# RUMP.net
KiCad netlist of a schematic drawn in EAGLE
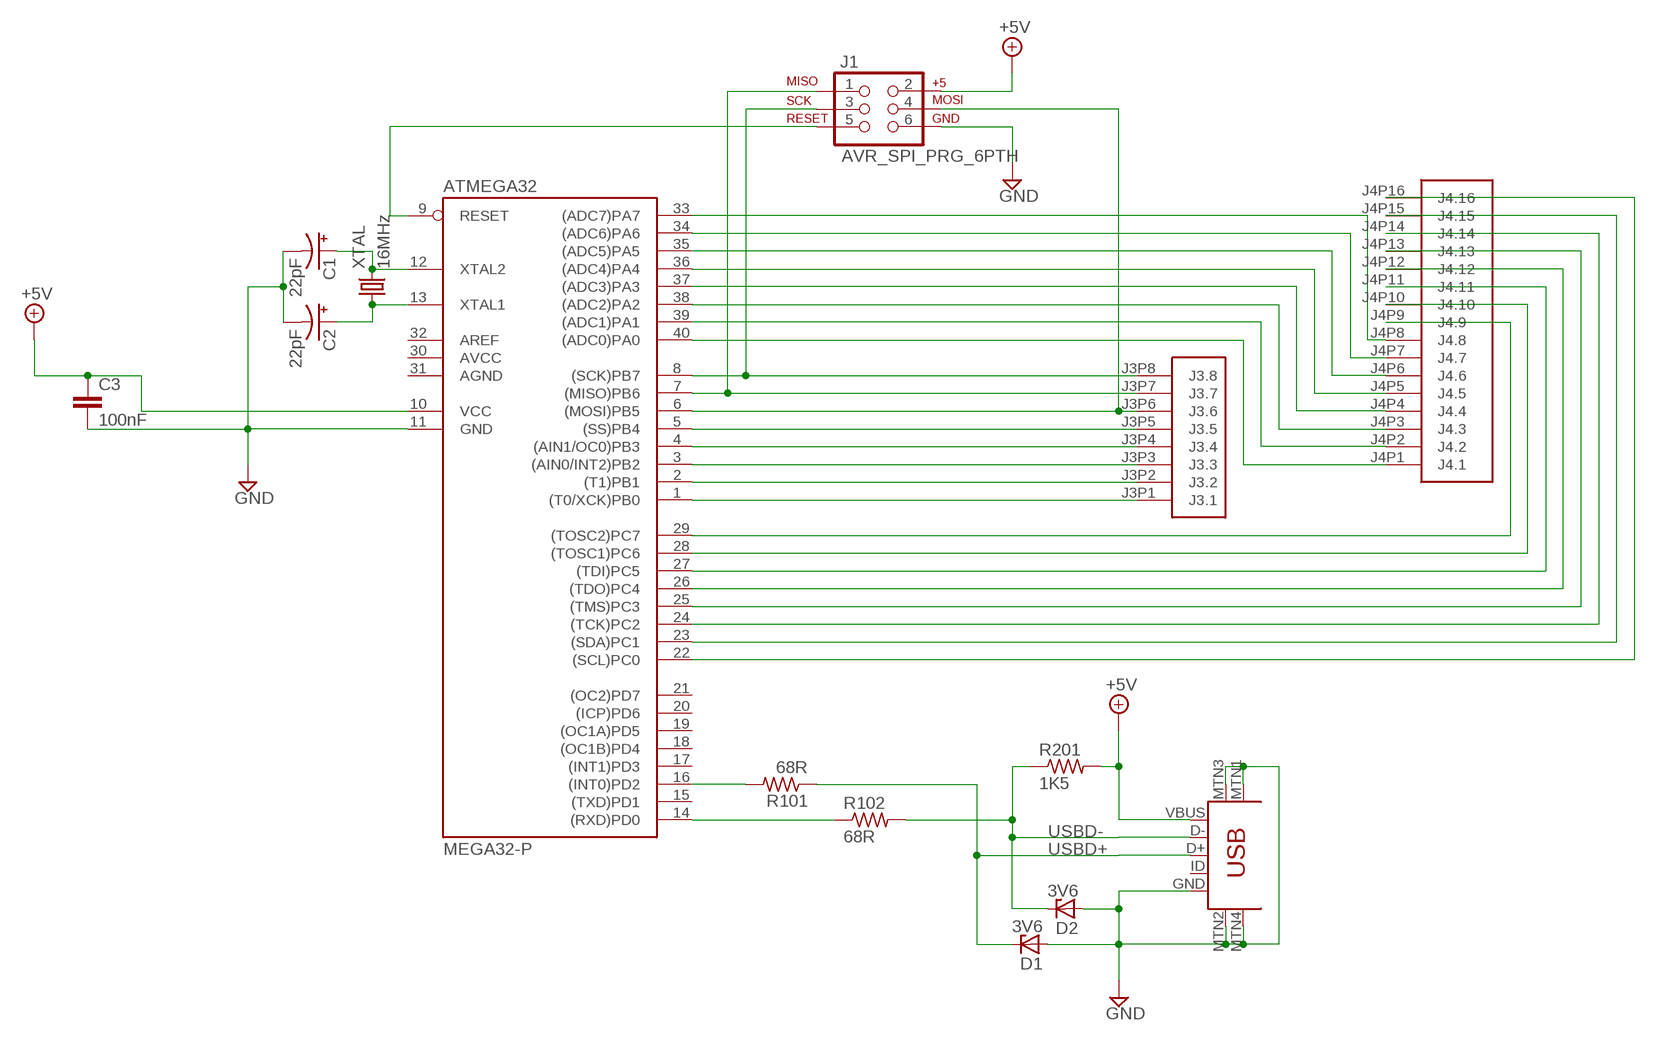
[diagram p0: schematic, sheet 1]

(export (version "E")
  (design (tool "Eeschema 10.0.6"))
  (components
    (comp (ref "ATMEGA32")
      (value "MEGA32-P")
      (footprint "eagle-import:DIL40")
      (libsource (lib "eagle-import") (part "MEGA32-P"))
    )
    (comp (ref "C1")
      (value "22pF")
      (footprint "eagle-import:E2-4")
      (libsource (lib "eagle-import") (part "CPOL-USE2-4"))
    )
    (comp (ref "C2")
      (value "22pF")
      (footprint "eagle-import:E2-4")
      (libsource (lib "eagle-import") (part "CPOL-USE2-4"))
    )
    (comp (ref "C3")
      (value "100nF")
      (footprint "eagle-import:C2.5-2")
      (libsource (lib "eagle-import") (part "C2.5/2"))
    )
    (comp (ref "D1")
      (value "3V6")
      (footprint "eagle-import:DO35Z10")
      (libsource (lib "eagle-import") (part "ZENER-DIODEDO35Z10"))
    )
    (comp (ref "D2")
      (value "3V6")
      (footprint "eagle-import:DO35Z10")
      (libsource (lib "eagle-import") (part "ZENER-DIODEDO35Z10"))
    )
    (comp (ref "J1")
      (value "AVR_SPI_PRG_6PTH")
      (footprint "eagle-import:2X3")
      (libsource (lib "eagle-import") (part "AVR_SPI_PRG_6PTH"))
    )
    (comp (ref "R101")
      (value "68R")
      (footprint "eagle-import:0204_7")
      (libsource (lib "eagle-import") (part "R-US_0204/7"))
    )
    (comp (ref "R102")
      (value "68R")
      (footprint "eagle-import:0204_7")
      (libsource (lib "eagle-import") (part "R-US_0204/7"))
    )
    (comp (ref "R201")
      (value "1K5")
      (footprint "eagle-import:0204_7")
      (libsource (lib "eagle-import") (part "R-US_0204/7"))
    )
    (comp (ref "U$1")
      (value "MODEL-M-J3")
      (footprint "eagle-import:MODEL-M-J3")
      (libsource (lib "eagle-import") (part "MODEL-M-J3"))
    )
    (comp (ref "U$2")
      (value "MODEL-M-J4")
      (footprint "eagle-import:MODEL-M-J4")
      (libsource (lib "eagle-import") (part "MODEL-M-J4"))
    )
    (comp (ref "U$3")
      (value "USB-MINIB-5PIN")
      (footprint "eagle-import:USB-MINIB")
      (libsource (lib "eagle-import") (part "USB-MINIB-5PIN"))
    )
    (comp (ref "XTAL")
      (value "16MHz")
      (footprint "eagle-import:HC49_S")
      (libsource (lib "eagle-import") (part "CRYSTALHC49S"))
    )
  )
  (nets
    (net (code "1") (name "+5V") (class "Default")
      (node (ref "ATMEGA32") (pin "10") (pinfunction "VCC_10") (pintype "power_in"))
      (node (ref "C3") (pin "1") (pinfunction "1_1") (pintype "passive"))
      (node (ref "J1") (pin "2") (pinfunction "2_2") (pintype "passive"))
      (node (ref "R201") (pin "2") (pinfunction "2_2") (pintype "passive"))
      (node (ref "U$3") (pin "VBUS") (pinfunction "VBUS_VBUS") (pintype "bidirectional"))
    )
    (net (code "2") (name "/AGND") (class "Default")
      (node (ref "ATMEGA32") (pin "31") (pinfunction "AGND_31") (pintype "power_in"))
    )
    (net (code "3") (name "/AVCC") (class "Default")
      (node (ref "ATMEGA32") (pin "30") (pinfunction "AVCC_30") (pintype "power_in"))
    )
    (net (code "4") (name "/USBD+") (class "Default")
      (node (ref "D1") (pin "C") (pinfunction "C_C") (pintype "passive"))
      (node (ref "R101") (pin "1") (pinfunction "1_1") (pintype "passive"))
      (node (ref "U$3") (pin "D+") (pinfunction "D+_D+") (pintype "bidirectional"))
    )
    (net (code "5") (name "/USBD-") (class "Default")
      (node (ref "D2") (pin "C") (pinfunction "C_C") (pintype "passive"))
      (node (ref "R102") (pin "2") (pinfunction "2_2") (pintype "passive"))
      (node (ref "R201") (pin "1") (pinfunction "1_1") (pintype "passive"))
      (node (ref "U$3") (pin "D-") (pinfunction "D-_D-") (pintype "bidirectional"))
    )
    (net (code "6") (name "GND") (class "Default")
      (node (ref "ATMEGA32") (pin "11") (pinfunction "GND_11") (pintype "power_in"))
      (node (ref "C1") (pin "-") (pinfunction "-_-") (pintype "passive"))
      (node (ref "C2") (pin "-") (pinfunction "-_-") (pintype "passive"))
      (node (ref "C3") (pin "2") (pinfunction "2_2") (pintype "passive"))
      (node (ref "D1") (pin "A") (pinfunction "A_A") (pintype "passive"))
      (node (ref "D2") (pin "A") (pinfunction "A_A") (pintype "passive"))
      (node (ref "J1") (pin "6") (pinfunction "6_6") (pintype "passive"))
      (node (ref "U$3") (pin "GND") (pinfunction "GND_GND") (pintype "bidirectional"))
      (node (ref "U$3") (pin "MTN1") (pinfunction "MTN2_MTN1") (pintype "bidirectional"))
      (node (ref "U$3") (pin "MTN2") (pinfunction "MTN3_MTN2") (pintype "bidirectional"))
      (node (ref "U$3") (pin "MTN3") (pinfunction "MTN1_MTN3") (pintype "bidirectional"))
      (node (ref "U$3") (pin "MTN4") (pinfunction "MTN4_MTN4") (pintype "bidirectional"))
    )
    (net (code "7") (name "Net-(ATMEGA32-(ADC0)PA0)") (class "Default")
      (node (ref "ATMEGA32") (pin "40") (pinfunction "(ADC0)PA0_40") (pintype "bidirectional"))
      (node (ref "U$2") (pin "J4P1") (pinfunction "J4.1_J4P1") (pintype "bidirectional"))
    )
    (net (code "8") (name "Net-(ATMEGA32-(ADC1)PA1)") (class "Default")
      (node (ref "ATMEGA32") (pin "39") (pinfunction "(ADC1)PA1_39") (pintype "bidirectional"))
      (node (ref "U$2") (pin "J4P2") (pinfunction "J4.2_J4P2") (pintype "bidirectional"))
    )
    (net (code "9") (name "Net-(ATMEGA32-(ADC2)PA2)") (class "Default")
      (node (ref "ATMEGA32") (pin "38") (pinfunction "(ADC2)PA2_38") (pintype "bidirectional"))
      (node (ref "U$2") (pin "J4P3") (pinfunction "J4.3_J4P3") (pintype "bidirectional"))
    )
    (net (code "10") (name "Net-(ATMEGA32-(ADC3)PA3)") (class "Default")
      (node (ref "ATMEGA32") (pin "37") (pinfunction "(ADC3)PA3_37") (pintype "bidirectional"))
      (node (ref "U$2") (pin "J4P4") (pinfunction "J4.4_J4P4") (pintype "bidirectional"))
    )
    (net (code "11") (name "Net-(ATMEGA32-(ADC4)PA4)") (class "Default")
      (node (ref "ATMEGA32") (pin "36") (pinfunction "(ADC4)PA4_36") (pintype "bidirectional"))
      (node (ref "U$2") (pin "J4P5") (pinfunction "J4.5_J4P5") (pintype "bidirectional"))
    )
    (net (code "12") (name "Net-(ATMEGA32-(ADC5)PA5)") (class "Default")
      (node (ref "ATMEGA32") (pin "35") (pinfunction "(ADC5)PA5_35") (pintype "bidirectional"))
      (node (ref "U$2") (pin "J4P6") (pinfunction "J4.6_J4P6") (pintype "bidirectional"))
    )
    (net (code "13") (name "Net-(ATMEGA32-(ADC6)PA6)") (class "Default")
      (node (ref "ATMEGA32") (pin "34") (pinfunction "(ADC6)PA6_34") (pintype "bidirectional"))
      (node (ref "U$2") (pin "J4P7") (pinfunction "J4.7_J4P7") (pintype "bidirectional"))
    )
    (net (code "14") (name "Net-(ATMEGA32-(ADC7)PA7)") (class "Default")
      (node (ref "ATMEGA32") (pin "33") (pinfunction "(ADC7)PA7_33") (pintype "bidirectional"))
      (node (ref "U$2") (pin "J4P8") (pinfunction "J4.8_J4P8") (pintype "bidirectional"))
    )
    (net (code "15") (name "Net-(ATMEGA32-(AIN0{slash}INT2)PB2)") (class "Default")
      (node (ref "ATMEGA32") (pin "3") (pinfunction "(AIN0/INT2)PB2_3") (pintype "bidirectional"))
      (node (ref "U$1") (pin "J3P3") (pinfunction "J3.3_J3P3") (pintype "bidirectional"))
    )
    (net (code "16") (name "Net-(ATMEGA32-(AIN1{slash}OC0)PB3)") (class "Default")
      (node (ref "ATMEGA32") (pin "4") (pinfunction "(AIN1/OC0)PB3_4") (pintype "bidirectional"))
      (node (ref "U$1") (pin "J3P4") (pinfunction "J3.4_J3P4") (pintype "bidirectional"))
    )
    (net (code "17") (name "Net-(ATMEGA32-(INT0)PD2)") (class "Default")
      (node (ref "ATMEGA32") (pin "16") (pinfunction "(INT0)PD2_16") (pintype "bidirectional"))
      (node (ref "R101") (pin "2") (pinfunction "2_2") (pintype "passive"))
    )
    (net (code "18") (name "Net-(ATMEGA32-(MISO)PB6)") (class "Default")
      (node (ref "ATMEGA32") (pin "7") (pinfunction "(MISO)PB6_7") (pintype "bidirectional"))
      (node (ref "J1") (pin "1") (pinfunction "1_1") (pintype "passive"))
      (node (ref "U$1") (pin "J3P7") (pinfunction "J3.7_J3P7") (pintype "bidirectional"))
    )
    (net (code "19") (name "Net-(ATMEGA32-(MOSI)PB5)") (class "Default")
      (node (ref "ATMEGA32") (pin "6") (pinfunction "(MOSI)PB5_6") (pintype "bidirectional"))
      (node (ref "J1") (pin "4") (pinfunction "4_4") (pintype "passive"))
      (node (ref "U$1") (pin "J3P6") (pinfunction "J3.6_J3P6") (pintype "bidirectional"))
    )
    (net (code "20") (name "Net-(ATMEGA32-(RXD)PD0)") (class "Default")
      (node (ref "ATMEGA32") (pin "14") (pinfunction "(RXD)PD0_14") (pintype "bidirectional"))
      (node (ref "R102") (pin "1") (pinfunction "1_1") (pintype "passive"))
    )
    (net (code "21") (name "Net-(ATMEGA32-(SCK)PB7)") (class "Default")
      (node (ref "ATMEGA32") (pin "8") (pinfunction "(SCK)PB7_8") (pintype "bidirectional"))
      (node (ref "J1") (pin "3") (pinfunction "3_3") (pintype "passive"))
      (node (ref "U$1") (pin "J3P8") (pinfunction "J3.8_J3P8") (pintype "bidirectional"))
    )
    (net (code "22") (name "Net-(ATMEGA32-(SCL)PC0)") (class "Default")
      (node (ref "ATMEGA32") (pin "22") (pinfunction "(SCL)PC0_22") (pintype "bidirectional"))
      (node (ref "U$2") (pin "J4P16") (pinfunction "J4.16_J4P16") (pintype "bidirectional"))
    )
    (net (code "23") (name "Net-(ATMEGA32-(SDA)PC1)") (class "Default")
      (node (ref "ATMEGA32") (pin "23") (pinfunction "(SDA)PC1_23") (pintype "bidirectional"))
      (node (ref "U$2") (pin "J4P15") (pinfunction "J4.15_J4P15") (pintype "bidirectional"))
    )
    (net (code "24") (name "Net-(ATMEGA32-(SS)PB4)") (class "Default")
      (node (ref "ATMEGA32") (pin "5") (pinfunction "(SS)PB4_5") (pintype "bidirectional"))
      (node (ref "U$1") (pin "J3P5") (pinfunction "J3.5_J3P5") (pintype "bidirectional"))
    )
    (net (code "25") (name "Net-(ATMEGA32-(T0{slash}XCK)PB0)") (class "Default")
      (node (ref "ATMEGA32") (pin "1") (pinfunction "(T0/XCK)PB0_1") (pintype "bidirectional"))
      (node (ref "U$1") (pin "J3P1") (pinfunction "J3.1_J3P1") (pintype "bidirectional"))
    )
    (net (code "26") (name "Net-(ATMEGA32-(T1)PB1)") (class "Default")
      (node (ref "ATMEGA32") (pin "2") (pinfunction "(T1)PB1_2") (pintype "bidirectional"))
      (node (ref "U$1") (pin "J3P2") (pinfunction "J3.2_J3P2") (pintype "bidirectional"))
    )
    (net (code "27") (name "Net-(ATMEGA32-(TCK)PC2)") (class "Default")
      (node (ref "ATMEGA32") (pin "24") (pinfunction "(TCK)PC2_24") (pintype "bidirectional"))
      (node (ref "U$2") (pin "J4P14") (pinfunction "J4.14_J4P14") (pintype "bidirectional"))
    )
    (net (code "28") (name "Net-(ATMEGA32-(TDI)PC5)") (class "Default")
      (node (ref "ATMEGA32") (pin "27") (pinfunction "(TDI)PC5_27") (pintype "bidirectional"))
      (node (ref "U$2") (pin "J4P11") (pinfunction "J4.11_J4P11") (pintype "bidirectional"))
    )
    (net (code "29") (name "Net-(ATMEGA32-(TDO)PC4)") (class "Default")
      (node (ref "ATMEGA32") (pin "26") (pinfunction "(TDO)PC4_26") (pintype "bidirectional"))
      (node (ref "U$2") (pin "J4P12") (pinfunction "J4.12_J4P12") (pintype "bidirectional"))
    )
    (net (code "30") (name "Net-(ATMEGA32-(TMS)PC3)") (class "Default")
      (node (ref "ATMEGA32") (pin "25") (pinfunction "(TMS)PC3_25") (pintype "bidirectional"))
      (node (ref "U$2") (pin "J4P13") (pinfunction "J4.13_J4P13") (pintype "bidirectional"))
    )
    (net (code "31") (name "Net-(ATMEGA32-(TOSC1)PC6)") (class "Default")
      (node (ref "ATMEGA32") (pin "28") (pinfunction "(TOSC1)PC6_28") (pintype "bidirectional"))
      (node (ref "U$2") (pin "J4P10") (pinfunction "J4.10_J4P10") (pintype "bidirectional"))
    )
    (net (code "32") (name "Net-(ATMEGA32-(TOSC2)PC7)") (class "Default")
      (node (ref "ATMEGA32") (pin "29") (pinfunction "(TOSC2)PC7_29") (pintype "bidirectional"))
      (node (ref "U$2") (pin "J4P9") (pinfunction "J4.9_J4P9") (pintype "bidirectional"))
    )
    (net (code "33") (name "Net-(ATMEGA32-RESET)") (class "Default")
      (node (ref "ATMEGA32") (pin "9") (pinfunction "RESET_9") (pintype "input"))
      (node (ref "J1") (pin "5") (pinfunction "5_5") (pintype "passive"))
    )
    (net (code "34") (name "Net-(ATMEGA32-XTAL1)") (class "Default")
      (node (ref "ATMEGA32") (pin "13") (pinfunction "XTAL1_13") (pintype "bidirectional"))
      (node (ref "C2") (pin "+") (pinfunction "+_+") (pintype "passive"))
      (node (ref "XTAL") (pin "1") (pinfunction "1_1") (pintype "passive"))
    )
    (net (code "35") (name "Net-(ATMEGA32-XTAL2)") (class "Default")
      (node (ref "ATMEGA32") (pin "12") (pinfunction "XTAL2_12") (pintype "bidirectional"))
      (node (ref "C1") (pin "+") (pinfunction "+_+") (pintype "passive"))
      (node (ref "XTAL") (pin "2") (pinfunction "2_2") (pintype "passive"))
    )
    (net (code "36") (name "unconnected-(ATMEGA32-(ICP)PD6-Pad20)") (class "Default")
      (node (ref "ATMEGA32") (pin "20") (pinfunction "(ICP)PD6_20") (pintype "bidirectional"))
    )
    (net (code "37") (name "unconnected-(ATMEGA32-(INT1)PD3-Pad17)") (class "Default")
      (node (ref "ATMEGA32") (pin "17") (pinfunction "(INT1)PD3_17") (pintype "bidirectional"))
    )
    (net (code "38") (name "unconnected-(ATMEGA32-(OC1A)PD5-Pad19)") (class "Default")
      (node (ref "ATMEGA32") (pin "19") (pinfunction "(OC1A)PD5_19") (pintype "bidirectional"))
    )
    (net (code "39") (name "unconnected-(ATMEGA32-(OC1B)PD4-Pad18)") (class "Default")
      (node (ref "ATMEGA32") (pin "18") (pinfunction "(OC1B)PD4_18") (pintype "bidirectional"))
    )
    (net (code "40") (name "unconnected-(ATMEGA32-(OC2)PD7-Pad21)") (class "Default")
      (node (ref "ATMEGA32") (pin "21") (pinfunction "(OC2)PD7_21") (pintype "bidirectional"))
    )
    (net (code "41") (name "unconnected-(ATMEGA32-(TXD)PD1-Pad15)") (class "Default")
      (node (ref "ATMEGA32") (pin "15") (pinfunction "(TXD)PD1_15") (pintype "bidirectional"))
    )
    (net (code "42") (name "unconnected-(ATMEGA32-AREF-Pad32)") (class "Default")
      (node (ref "ATMEGA32") (pin "32") (pinfunction "AREF_32") (pintype "passive"))
    )
    (net (code "43") (name "unconnected-(U$3-PadID)") (class "Default")
      (node (ref "U$3") (pin "ID") (pinfunction "ID_ID") (pintype "bidirectional"))
    )
  )
)
